# battery-charging.net
KiCad netlist of a schematic drawn in Altium Designer
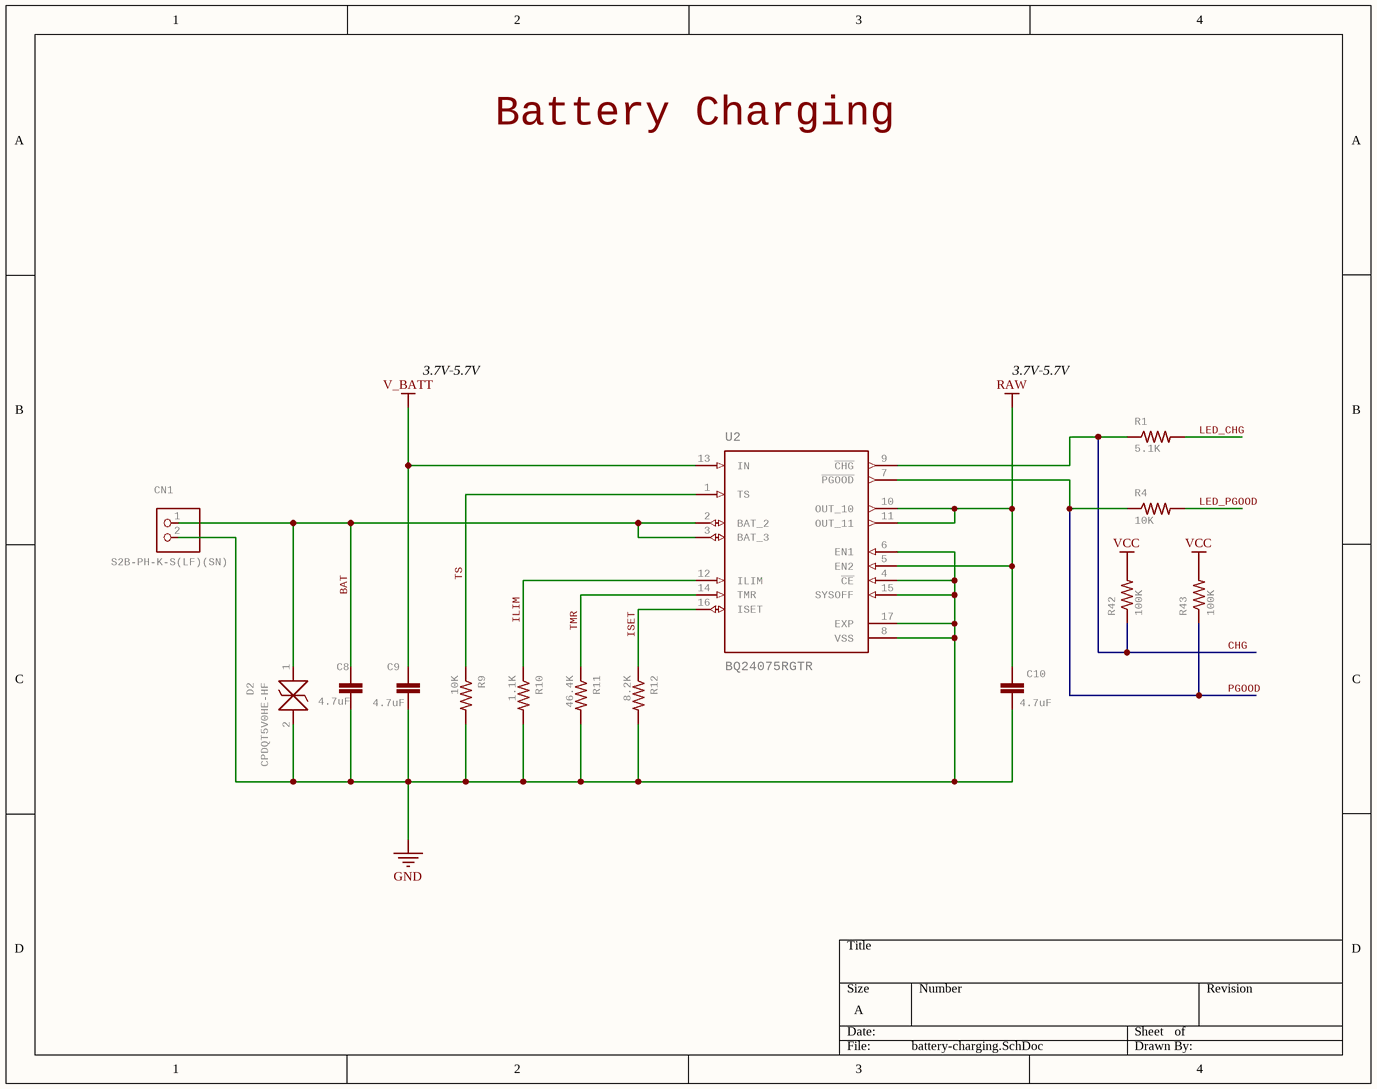
[diagram p0: battery-charging.SchDoc]

(export (version "E")
  (design (tool "Eeschema 10.0.6"))
  (components
    (comp (ref "C8")
      (value "4.7uF")
      (footprint "0402-CAP")
      (description "CapacitorStandard 0603 ceramic capacitor, and 0.1\" leaded capacitor.")
      (fields (field (name "MPN") "JMK105BBJ475MV-F"))
      (libsource (lib "rt10") (part "CAP0402-CAP"))
    )
    (comp (ref "C9")
      (value "4.7uF")
      (footprint "0402-CAP")
      (description "CapacitorStandard 0603 ceramic capacitor, and 0.1\" leaded capacitor.")
      (fields (field (name "MPN") "JMK105BBJ475MV-F"))
      (libsource (lib "rt10") (part "CAP0402-CAP"))
    )
    (comp (ref "C10")
      (value "4.7uF")
      (footprint "0402-CAP")
      (description "CapacitorStandard 0603 ceramic capacitor, and 0.1\" leaded capacitor.")
      (fields (field (name "MPN") "JMK105BBJ475MV-F"))
      (libsource (lib "rt10") (part "CAP0402-CAP"))
    )
    (comp (ref "CN1")
      (value "S2B-PH-K-S(LF)(SN)")
      (footprint "JST-PH-2-THM-RA")
      (fields (field (name "LIBRARYNAME") "adafruit-updated"))
      (libsource (lib "rt10") (part "JST_2PIN-THM-RA"))
    )
    (comp (ref "D2")
      (value "CPDQT5V0HE-HF")
      (footprint "CPDQT5V0HEHF")
      (description "ESD Suppressors / TVS Diodes DIODE ESD 5VWM 65W 0402/SOD-923F   Source:  Datasheet")
      (fields (field (name "MOUSER_PART_NUMBER") "MOUSER_PART_NUMBER"))
      (libsource (lib "rt10") (part "CPDQT5V0HE-HF"))
    )
    (comp (ref "R1")
      (value "5.1K")
      (footprint "0402-RES")
      (description "ResistorBasic schematic elements and footprints for 0603, 1206, and PTH resistors.")
      (fields (field (name "MPN") "RC0402JR-075K1L"))
      (libsource (lib "rt10") (part "RESISTOR0402-RES"))
    )
    (comp (ref "R4")
      (value "10K")
      (footprint "0402-RES")
      (description "ResistorBasic schematic elements and footprints for 0603, 1206, and PTH resistors.")
      (fields (field (name "MPN") "AC0402FR-1310KL"))
      (libsource (lib "rt10") (part "RESISTOR0402-RES"))
    )
    (comp (ref "R9")
      (value "10K")
      (footprint "0402-RES")
      (description "ResistorBasic schematic elements and footprints for 0603, 1206, and PTH resistors.")
      (fields (field (name "MPN") "AC0402FR-1310KL"))
      (libsource (lib "rt10") (part "RESISTOR0402-RES"))
    )
    (comp (ref "R10")
      (value "1.1K")
      (footprint "0402-RES")
      (description "ResistorBasic schematic elements and footprints for 0603, 1206, and PTH resistors.")
      (fields (field (name "MPN") "RC0402JR-071K1"))
      (libsource (lib "rt10") (part "RESISTOR0402-RES"))
    )
    (comp (ref "R11")
      (value "46.4K")
      (footprint "0402-RES")
      (description "ResistorBasic schematic elements and footprints for 0603, 1206, and PTH resistors.")
      (fields (field (name "MPN") "WR04X4642FTL"))
      (libsource (lib "rt10") (part "RESISTOR0402-RES"))
    )
    (comp (ref "R12")
      (value "8.2K")
      (footprint "0402-RES")
      (description "ResistorBasic schematic elements and footprints for 0603, 1206, and PTH resistors.")
      (fields (field (name "MPN") "CR0402-FX-8201GLF"))
      (libsource (lib "rt10") (part "RESISTOR0402-RES"))
    )
    (comp (ref "R42")
      (value "100K")
      (footprint "0402-RES")
      (description "ResistorBasic schematic elements and footprints for 0603, 1206, and PTH resistors.")
      (fields (field (name "MPN") "AC0402FR-07100KL"))
      (libsource (lib "rt10") (part "RESISTOR0402-RES"))
    )
    (comp (ref "R43")
      (value "100K")
      (footprint "0402-RES")
      (description "ResistorBasic schematic elements and footprints for 0603, 1206, and PTH resistors.")
      (fields (field (name "MPN") "AC0402FR-07100KL"))
      (libsource (lib "rt10") (part "RESISTOR0402-RES"))
    )
    (comp (ref "U2")
      (value "BQ24075RGTR")
      (footprint "QFN50P300X300X100-17N")
      (fields (field (name "MF") "Texas Instruments"))
      (libsource (lib "rt10") (part "BQ24075RGTR"))
    )
  )
  (nets
    (net (code "1") (name "/BAT") (class "Default")
      (node (ref "C8") (pin "2") (pinfunction "2_2") (pintype "passive"))
      (node (ref "CN1") (pin "1") (pinfunction "2_1") (pintype "passive"))
      (node (ref "D2") (pin "1") (pinfunction "1_1") (pintype "bidirectional"))
      (node (ref "U2") (pin "2") (pinfunction "BAT_2_2") (pintype "bidirectional"))
      (node (ref "U2") (pin "3") (pinfunction "BAT_3_3") (pintype "bidirectional"))
    )
    (net (code "2") (name "/CHG") (class "Default")
      (node (ref "R1") (pin "1") (pinfunction "1_1") (pintype "passive"))
      (node (ref "R42") (pin "1") (pinfunction "1_1") (pintype "passive"))
      (node (ref "U2") (pin "9") (pinfunction "~{CHG}_9") (pintype "output"))
    )
    (net (code "3") (name "/ILIM") (class "Default")
      (node (ref "R10") (pin "1") (pinfunction "1_1") (pintype "passive"))
      (node (ref "U2") (pin "12") (pinfunction "ILIM_12") (pintype "input"))
    )
    (net (code "4") (name "/ISET") (class "Default")
      (node (ref "R12") (pin "1") (pinfunction "1_1") (pintype "passive"))
      (node (ref "U2") (pin "16") (pinfunction "ISET_16") (pintype "bidirectional"))
    )
    (net (code "5") (name "/LED_CHG") (class "Default")
      (node (ref "R1") (pin "2") (pinfunction "2_2") (pintype "passive"))
    )
    (net (code "6") (name "/LED_PGOOD") (class "Default")
      (node (ref "R4") (pin "2") (pinfunction "2_2") (pintype "passive"))
    )
    (net (code "7") (name "/PGOOD") (class "Default")
      (node (ref "R4") (pin "1") (pinfunction "1_1") (pintype "passive"))
      (node (ref "R43") (pin "1") (pinfunction "1_1") (pintype "passive"))
      (node (ref "U2") (pin "7") (pinfunction "~{PGOOD}_7") (pintype "output"))
    )
    (net (code "8") (name "/TMR") (class "Default")
      (node (ref "R11") (pin "1") (pinfunction "1_1") (pintype "passive"))
      (node (ref "U2") (pin "14") (pinfunction "TMR_14") (pintype "input"))
    )
    (net (code "9") (name "/TS") (class "Default")
      (node (ref "R9") (pin "1") (pinfunction "1_1") (pintype "passive"))
      (node (ref "U2") (pin "1") (pinfunction "TS_1") (pintype "input"))
    )
    (net (code "10") (name "GND") (class "Default")
      (node (ref "C10") (pin "1") (pinfunction "1_1") (pintype "passive"))
      (node (ref "C8") (pin "1") (pinfunction "1_1") (pintype "passive"))
      (node (ref "C9") (pin "1") (pinfunction "1_1") (pintype "passive"))
      (node (ref "CN1") (pin "2") (pinfunction "1_2") (pintype "passive"))
      (node (ref "D2") (pin "2") (pinfunction "2_2") (pintype "bidirectional"))
      (node (ref "R10") (pin "2") (pinfunction "2_2") (pintype "passive"))
      (node (ref "R11") (pin "2") (pinfunction "2_2") (pintype "passive"))
      (node (ref "R12") (pin "2") (pinfunction "2_2") (pintype "passive"))
      (node (ref "R9") (pin "2") (pinfunction "2_2") (pintype "passive"))
      (node (ref "U2") (pin "15") (pinfunction "SYSOFF_15") (pintype "input"))
      (node (ref "U2") (pin "17") (pinfunction "EXP_17") (pintype "power_in"))
      (node (ref "U2") (pin "4") (pinfunction "~{CE}_4") (pintype "input"))
      (node (ref "U2") (pin "6") (pinfunction "EN1_6") (pintype "input"))
      (node (ref "U2") (pin "8") (pinfunction "VSS_8") (pintype "power_in"))
    )
    (net (code "11") (name "RAW") (class "Default")
      (node (ref "C10") (pin "2") (pinfunction "2_2") (pintype "passive"))
      (node (ref "U2") (pin "10") (pinfunction "OUT_10_10") (pintype "output"))
      (node (ref "U2") (pin "11") (pinfunction "OUT_11_11") (pintype "output"))
      (node (ref "U2") (pin "5") (pinfunction "EN2_5") (pintype "input"))
    )
    (net (code "12") (name "VCC") (class "Default")
      (node (ref "R42") (pin "2") (pinfunction "2_2") (pintype "passive"))
      (node (ref "R43") (pin "2") (pinfunction "2_2") (pintype "passive"))
    )
    (net (code "13") (name "V_BATT") (class "Default")
      (node (ref "C9") (pin "2") (pinfunction "2_2") (pintype "passive"))
      (node (ref "U2") (pin "13") (pinfunction "IN_13") (pintype "input"))
    )
  )
)
